# parrot_v2.net
KiCad netlist of a schematic drawn in EAGLE
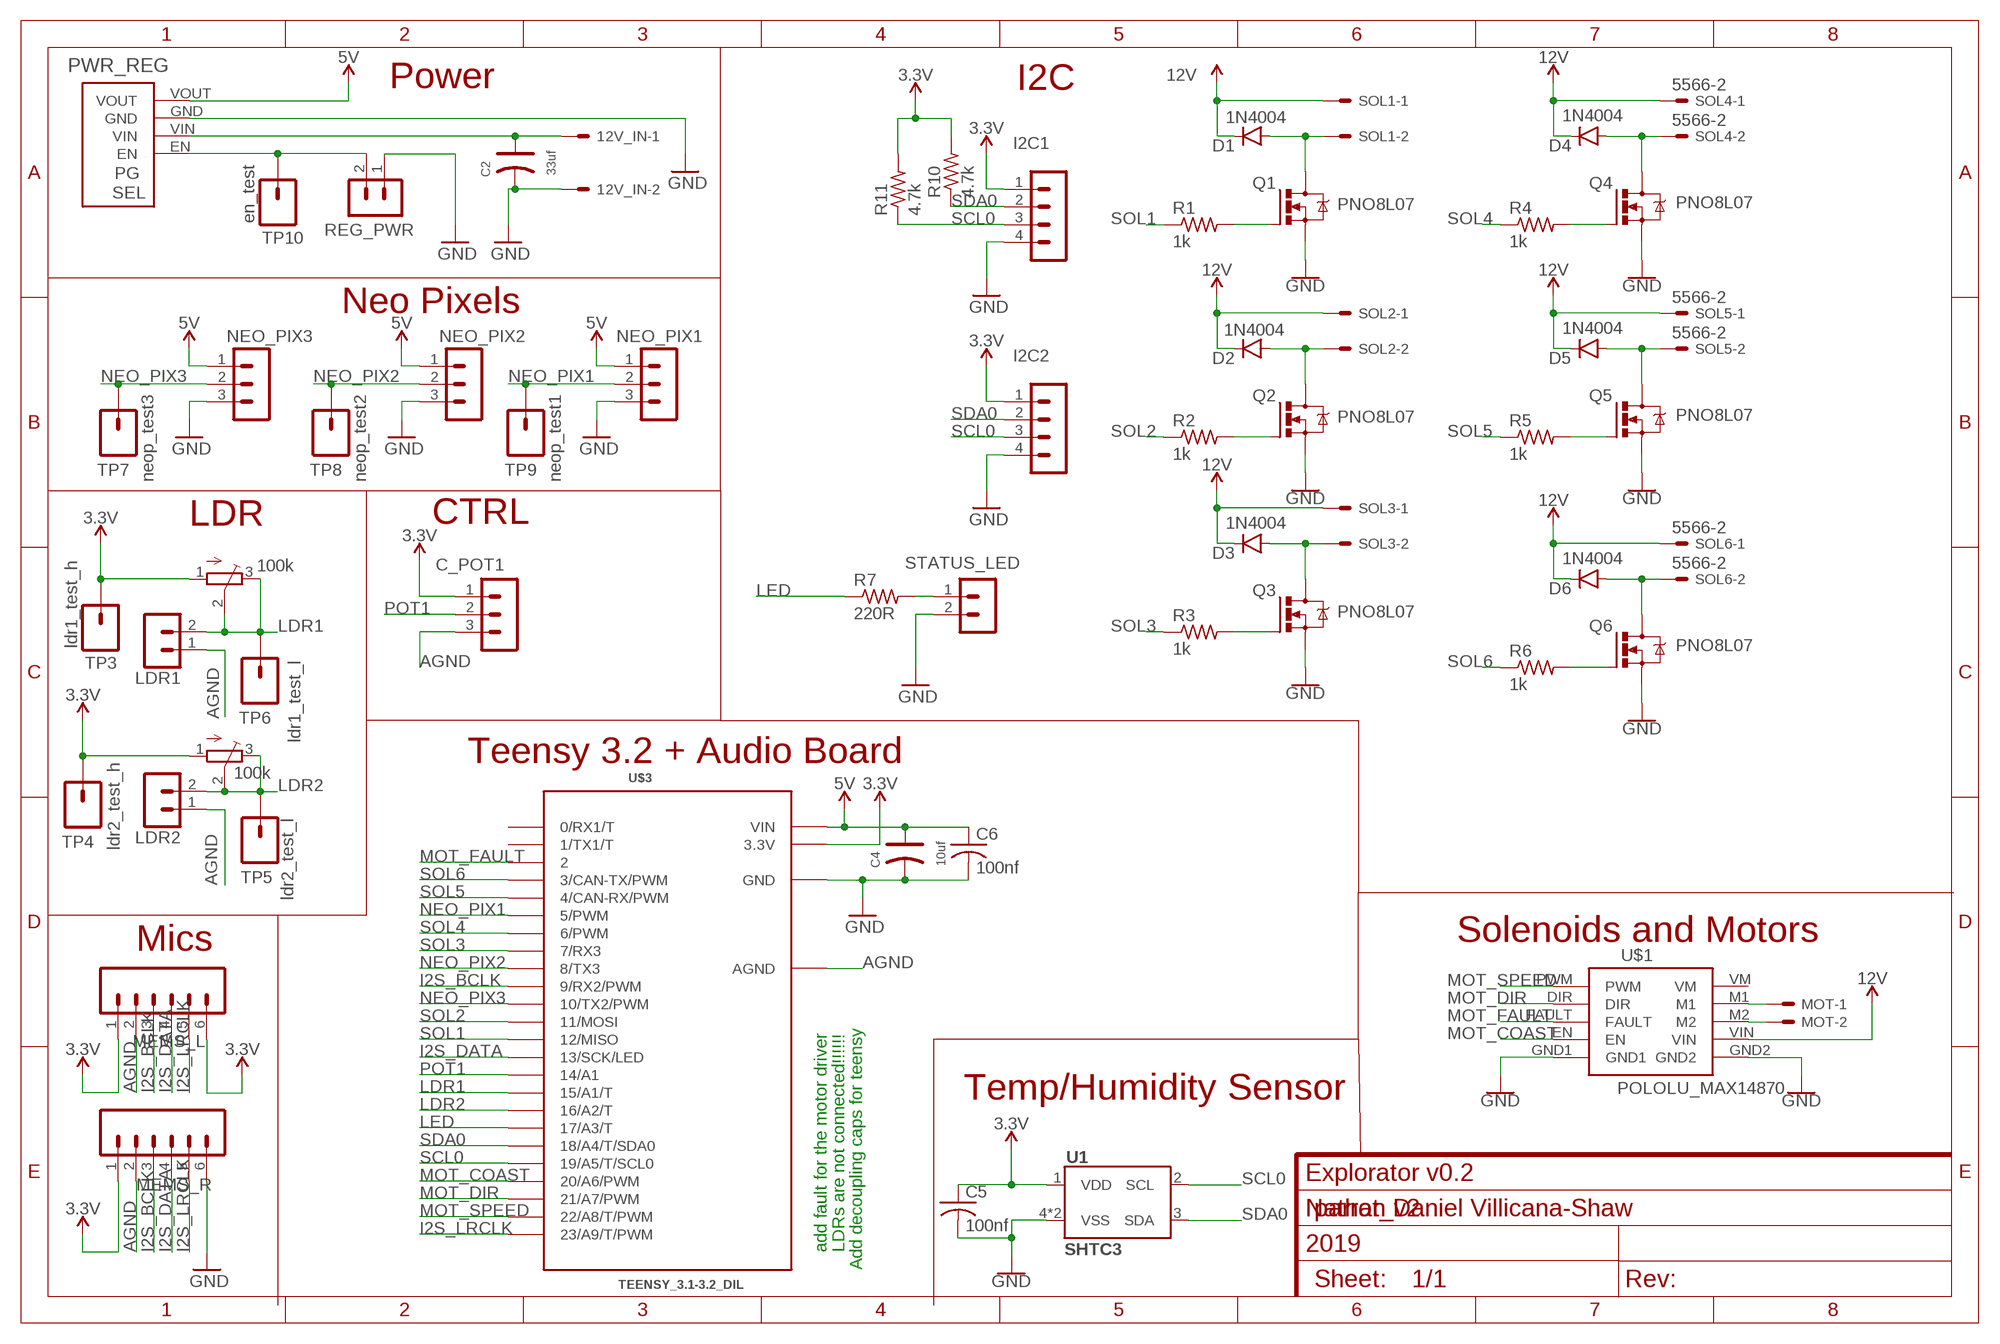
[diagram p0: schematic, sheet 1]

(export (version "E")
  (design (tool "Eeschema 10.0.6"))
  (components
    (comp (ref "12V_IN")
      (value "5566-2")
      (footprint "eagle-import:5566-2")
      (fields (field (name "MF") "MOLEX"))
      (libsource (lib "eagle-import") (part "5566-2"))
    )
    (comp (ref "C2")
      (value "33uf")
      (footprint "eagle-import:PC-D5.3MM")
      (fields (field (name "MPN") "KS 100uF/16V"))
      (libsource (lib "eagle-import") (part "DIP-ALUMINUM-47UF-16V(D5-H7MM)"))
    )
    (comp (ref "C4")
      (value "10uf")
      (footprint "eagle-import:PC-D5.3MM")
      (fields (field (name "MPN") "KS 100uF/16V"))
      (libsource (lib "eagle-import") (part "DIP-ALUMINUM-47UF-16V(D5-H7MM)"))
    )
    (comp (ref "C5")
      (value "100nf")
      (footprint "eagle-import:C2012")
      (libsource (lib "eagle-import") (part "C-USC2012"))
    )
    (comp (ref "C6")
      (value "100nf")
      (footprint "eagle-import:C2012")
      (libsource (lib "eagle-import") (part "C-USC2012"))
    )
    (comp (ref "C_POT1")
      (value "B3B-PH-K")
      (footprint "eagle-import:B3B-PH-K")
      (libsource (lib "eagle-import") (part "B3B-PH-K"))
    )
    (comp (ref "D1")
      (value "1N4004")
      (footprint "eagle-import:DIODE-1N4001")
      (libsource (lib "eagle-import") (part "DIODEPTH"))
    )
    (comp (ref "D2")
      (value "1N4004")
      (footprint "eagle-import:DIODE-1N4001")
      (libsource (lib "eagle-import") (part "DIODEPTH"))
    )
    (comp (ref "D3")
      (value "1N4004")
      (footprint "eagle-import:DIODE-1N4001")
      (libsource (lib "eagle-import") (part "DIODEPTH"))
    )
    (comp (ref "D4")
      (value "1N4004")
      (footprint "eagle-import:DIODE-1N4001")
      (libsource (lib "eagle-import") (part "DIODEPTH"))
    )
    (comp (ref "D5")
      (value "1N4004")
      (footprint "eagle-import:DIODE-1N4001")
      (libsource (lib "eagle-import") (part "DIODEPTH"))
    )
    (comp (ref "D6")
      (value "1N4004")
      (footprint "eagle-import:DIODE-1N4001")
      (libsource (lib "eagle-import") (part "DIODEPTH"))
    )
    (comp (ref "I2C1")
      (value "B4B-PH-K")
      (footprint "eagle-import:B4B-PH-K")
      (libsource (lib "eagle-import") (part "B4B-PH-K"))
    )
    (comp (ref "I2C2")
      (value "B4B-PH-K")
      (footprint "eagle-import:B4B-PH-K")
      (libsource (lib "eagle-import") (part "B4B-PH-K"))
    )
    (comp (ref "LDR1")
      (value "B2B-PH-K")
      (footprint "eagle-import:B2B-PH-K")
      (libsource (lib "eagle-import") (part "B2B-PH-K"))
    )
    (comp (ref "LDR2")
      (value "B2B-PH-K")
      (footprint "eagle-import:B2B-PH-K")
      (libsource (lib "eagle-import") (part "B2B-PH-K"))
    )
    (comp (ref "MEMS_L")
      (value "CONN_06POLAR")
      (footprint "eagle-import:MOLEX-1X6")
      (libsource (lib "eagle-import") (part "CONN_06POLAR"))
    )
    (comp (ref "MEMS_R")
      (value "CONN_06POLAR")
      (footprint "eagle-import:MOLEX-1X6")
      (libsource (lib "eagle-import") (part "CONN_06POLAR"))
    )
    (comp (ref "MOT")
      (value "5566-2")
      (footprint "eagle-import:5566-2")
      (fields (field (name "MF") "MOLEX"))
      (libsource (lib "eagle-import") (part "5566-2"))
    )
    (comp (ref "NEO_PIX1")
      (value "B3B-PH-K")
      (footprint "eagle-import:B3B-PH-K")
      (libsource (lib "eagle-import") (part "B3B-PH-K"))
    )
    (comp (ref "NEO_PIX2")
      (value "B3B-PH-K")
      (footprint "eagle-import:B3B-PH-K")
      (libsource (lib "eagle-import") (part "B3B-PH-K"))
    )
    (comp (ref "NEO_PIX3")
      (value "B3B-PH-K")
      (footprint "eagle-import:B3B-PH-K")
      (libsource (lib "eagle-import") (part "B3B-PH-K"))
    )
    (comp (ref "PWR_REG")
      (value "S9V11F5S6CMA_MISSINIG_PINS")
      (footprint "eagle-import:S9V11F3S5CMA_MISSING_PINS")
      (libsource (lib "eagle-import") (part "S9V11F5S6CMA_MISSINIG_PINS"))
    )
    (comp (ref "Q1")
      (value "PNO8L07")
      (footprint "eagle-import:TO220BV")
      (libsource (lib "eagle-import") (part "IRF540"))
    )
    (comp (ref "Q2")
      (value "PNO8L07")
      (footprint "eagle-import:TO220BV")
      (libsource (lib "eagle-import") (part "IRF540"))
    )
    (comp (ref "Q3")
      (value "PNO8L07")
      (footprint "eagle-import:TO220BV")
      (libsource (lib "eagle-import") (part "IRF540"))
    )
    (comp (ref "Q4")
      (value "PNO8L07")
      (footprint "eagle-import:TO220BV")
      (libsource (lib "eagle-import") (part "IRF540"))
    )
    (comp (ref "Q5")
      (value "PNO8L07")
      (footprint "eagle-import:TO220BV")
      (libsource (lib "eagle-import") (part "IRF540"))
    )
    (comp (ref "Q6")
      (value "PNO8L07")
      (footprint "eagle-import:TO220BV")
      (libsource (lib "eagle-import") (part "IRF540"))
    )
    (comp (ref "R1")
      (value "1k")
      (footprint "eagle-import:M1206")
      (libsource (lib "eagle-import") (part "R-US_M1206"))
    )
    (comp (ref "R2")
      (value "1k")
      (footprint "eagle-import:M1206")
      (libsource (lib "eagle-import") (part "R-US_M1206"))
    )
    (comp (ref "R3")
      (value "1k")
      (footprint "eagle-import:M1206")
      (libsource (lib "eagle-import") (part "R-US_M1206"))
    )
    (comp (ref "R4")
      (value "1k")
      (footprint "eagle-import:M1206")
      (libsource (lib "eagle-import") (part "R-US_M1206"))
    )
    (comp (ref "R5")
      (value "1k")
      (footprint "eagle-import:M1206")
      (libsource (lib "eagle-import") (part "R-US_M1206"))
    )
    (comp (ref "R6")
      (value "1k")
      (footprint "eagle-import:M1206")
      (libsource (lib "eagle-import") (part "R-US_M1206"))
    )
    (comp (ref "R7")
      (value "220R")
      (footprint "eagle-import:M1206")
      (libsource (lib "eagle-import") (part "R-US_M1206"))
    )
    (comp (ref "R10")
      (value "4.7k")
      (footprint "eagle-import:M1206")
      (libsource (lib "eagle-import") (part "R-US_M1206"))
    )
    (comp (ref "R11")
      (value "4.7k")
      (footprint "eagle-import:M1206")
      (libsource (lib "eagle-import") (part "R-US_M1206"))
    )
    (comp (ref "REG_PWR")
      (value "B2B-PH-K")
      (footprint "eagle-import:B2B-PH-K")
      (libsource (lib "eagle-import") (part "B2B-PH-K"))
    )
    (comp (ref "SOL1")
      (value "5566-2")
      (footprint "eagle-import:5566-2")
      (fields (field (name "MF") "MOLEX"))
      (libsource (lib "eagle-import") (part "5566-2"))
    )
    (comp (ref "SOL2")
      (value "5566-2")
      (footprint "eagle-import:5566-2")
      (fields (field (name "MF") "MOLEX"))
      (libsource (lib "eagle-import") (part "5566-2"))
    )
    (comp (ref "SOL3")
      (value "5566-2")
      (footprint "eagle-import:5566-2")
      (fields (field (name "MF") "MOLEX"))
      (libsource (lib "eagle-import") (part "5566-2"))
    )
    (comp (ref "SOL4")
      (value "5566-2")
      (footprint "eagle-import:5566-2")
      (fields (field (name "MF") "MOLEX"))
      (libsource (lib "eagle-import") (part "5566-2"))
    )
    (comp (ref "SOL5")
      (value "5566-2")
      (footprint "eagle-import:5566-2")
      (fields (field (name "MF") "MOLEX"))
      (libsource (lib "eagle-import") (part "5566-2"))
    )
    (comp (ref "SOL6")
      (value "5566-2")
      (footprint "eagle-import:5566-2")
      (fields (field (name "MF") "MOLEX"))
      (libsource (lib "eagle-import") (part "5566-2"))
    )
    (comp (ref "STATUS_LED")
      (value "B2B-PH-K")
      (footprint "eagle-import:B2B-PH-K")
      (libsource (lib "eagle-import") (part "B2B-PH-K"))
    )
    (comp (ref "TM1")
      (value "100k")
      (footprint "eagle-import:TC33X")
      (libsource (lib "eagle-import") (part "TRIMPOTTC33X"))
    )
    (comp (ref "TM2")
      (value "100k")
      (footprint "eagle-import:TC33X")
      (libsource (lib "eagle-import") (part "TRIMPOTTC33X"))
    )
    (comp (ref "TP3")
      (value "ldr1_test_h")
      (footprint "eagle-import:1X01")
      (libsource (lib "eagle-import") (part "CONN_01"))
    )
    (comp (ref "TP4")
      (value "ldr2_test_h")
      (footprint "eagle-import:1X01")
      (libsource (lib "eagle-import") (part "CONN_01"))
    )
    (comp (ref "TP5")
      (value "ldr2_test_l")
      (footprint "eagle-import:1X01")
      (libsource (lib "eagle-import") (part "CONN_01"))
    )
    (comp (ref "TP6")
      (value "ldr1_test_l")
      (footprint "eagle-import:1X01")
      (libsource (lib "eagle-import") (part "CONN_01"))
    )
    (comp (ref "TP7")
      (value "neop_test3")
      (footprint "eagle-import:1X01")
      (libsource (lib "eagle-import") (part "CONN_01"))
    )
    (comp (ref "TP8")
      (value "neop_test2")
      (footprint "eagle-import:1X01")
      (libsource (lib "eagle-import") (part "CONN_01"))
    )
    (comp (ref "TP9")
      (value "neop_test1")
      (footprint "eagle-import:1X01")
      (libsource (lib "eagle-import") (part "CONN_01"))
    )
    (comp (ref "TP10")
      (value "en_test")
      (footprint "eagle-import:1X01")
      (libsource (lib "eagle-import") (part "CONN_01"))
    )
    (comp (ref "U$1")
      (value "POLOLU_MAX14870")
      (footprint "eagle-import:POLOLU_MAX14870")
      (libsource (lib "eagle-import") (part "POLOLU_MAX14870"))
    )
    (comp (ref "U$3")
      (value "TEENSY_3.1-3.2_DIL")
      (footprint "eagle-import:TEENSY_3.0-3.2&LC_DIL")
      (libsource (lib "eagle-import") (part "TEENSY_3.1-3.2_DIL"))
    )
    (comp (ref "U1")
      (value "SHTC3")
      (footprint "eagle-import:SHTC3")
      (libsource (lib "eagle-import") (part "SHTC3"))
    )
  )
  (nets
    (net (code "1") (name "/AGND") (class "Default")
      (node (ref "C_POT1") (pin "3") (pinfunction "3_3") (pintype "passive"))
      (node (ref "LDR1") (pin "1") (pinfunction "1_1") (pintype "passive"))
      (node (ref "LDR2") (pin "1") (pinfunction "1_1") (pintype "passive"))
      (node (ref "MEMS_L") (pin "2") (pinfunction "2_2") (pintype "passive"))
      (node (ref "MEMS_R") (pin "2") (pinfunction "2_2") (pintype "passive"))
      (node (ref "U$3") (pin "AGND") (pinfunction "AGND_AGND") (pintype "power_in"))
    )
    (net (code "2") (name "/I2S_BCLK") (class "Default")
      (node (ref "MEMS_L") (pin "3") (pinfunction "3_3") (pintype "passive"))
      (node (ref "MEMS_R") (pin "3") (pinfunction "3_3") (pintype "passive"))
      (node (ref "U$3") (pin "9") (pinfunction "9/RX2/PWM_9") (pintype "bidirectional"))
    )
    (net (code "3") (name "/I2S_DATA") (class "Default")
      (node (ref "MEMS_L") (pin "4") (pinfunction "4_4") (pintype "passive"))
      (node (ref "MEMS_R") (pin "4") (pinfunction "4_4") (pintype "passive"))
      (node (ref "U$3") (pin "13") (pinfunction "13/SCK/LED_13") (pintype "bidirectional"))
    )
    (net (code "4") (name "/I2S_LRCLK") (class "Default")
      (node (ref "MEMS_L") (pin "5") (pinfunction "5_5") (pintype "passive"))
      (node (ref "MEMS_R") (pin "5") (pinfunction "5_5") (pintype "passive"))
      (node (ref "U$3") (pin "23/A9") (pinfunction "23/A9/T/PWM_23/A9") (pintype "bidirectional"))
    )
    (net (code "5") (name "/LDR1") (class "Default")
      (node (ref "LDR1") (pin "2") (pinfunction "2_2") (pintype "passive"))
      (node (ref "TM1") (pin "2") (pinfunction "S_2") (pintype "passive"))
      (node (ref "TM1") (pin "3") (pinfunction "E_3") (pintype "passive"))
      (node (ref "TP6") (pin "1") (pinfunction "1_1") (pintype "passive"))
      (node (ref "U$3") (pin "15/A1") (pinfunction "15/A1/T_15/A1") (pintype "bidirectional"))
    )
    (net (code "6") (name "/LDR2") (class "Default")
      (node (ref "LDR2") (pin "2") (pinfunction "2_2") (pintype "passive"))
      (node (ref "TM2") (pin "2") (pinfunction "S_2") (pintype "passive"))
      (node (ref "TM2") (pin "3") (pinfunction "E_3") (pintype "passive"))
      (node (ref "TP5") (pin "1") (pinfunction "1_1") (pintype "passive"))
      (node (ref "U$3") (pin "16/A2") (pinfunction "16/A2/T_16/A2") (pintype "bidirectional"))
    )
    (net (code "7") (name "/LED") (class "Default")
      (node (ref "R7") (pin "1") (pinfunction "1_1") (pintype "passive"))
      (node (ref "U$3") (pin "17/A3") (pinfunction "17/A3/T_17/A3") (pintype "bidirectional"))
    )
    (net (code "8") (name "/MOT_COAST") (class "Default")
      (node (ref "U$1") (pin "EN") (pinfunction "EN_EN") (pintype "bidirectional"))
      (node (ref "U$3") (pin "20/A6") (pinfunction "20/A6/PWM_20/A6") (pintype "bidirectional"))
    )
    (net (code "9") (name "/MOT_DIR") (class "Default")
      (node (ref "U$1") (pin "DIR") (pinfunction "DIR_DIR") (pintype "bidirectional"))
      (node (ref "U$3") (pin "21/A7") (pinfunction "21/A7/PWM_21/A7") (pintype "bidirectional"))
    )
    (net (code "10") (name "/MOT_FAULT") (class "Default")
      (node (ref "U$1") (pin "FAULT") (pinfunction "FAULT_FAULT") (pintype "bidirectional"))
      (node (ref "U$3") (pin "2") (pinfunction "2_2") (pintype "bidirectional"))
    )
    (net (code "11") (name "/MOT_SPEED") (class "Default")
      (node (ref "U$1") (pin "PWM") (pinfunction "PWM_PWM") (pintype "bidirectional"))
      (node (ref "U$3") (pin "22/A8") (pinfunction "22/A8/T/PWM_22/A8") (pintype "bidirectional"))
    )
    (net (code "12") (name "/NEO_PIX1") (class "Default")
      (node (ref "NEO_PIX1") (pin "2") (pinfunction "2_2") (pintype "passive"))
      (node (ref "TP9") (pin "1") (pinfunction "1_1") (pintype "passive"))
      (node (ref "U$3") (pin "5") (pinfunction "5/PWM_5") (pintype "bidirectional"))
    )
    (net (code "13") (name "/NEO_PIX2") (class "Default")
      (node (ref "NEO_PIX2") (pin "2") (pinfunction "2_2") (pintype "passive"))
      (node (ref "TP8") (pin "1") (pinfunction "1_1") (pintype "passive"))
      (node (ref "U$3") (pin "8") (pinfunction "8/TX3_8") (pintype "bidirectional"))
    )
    (net (code "14") (name "/NEO_PIX3") (class "Default")
      (node (ref "NEO_PIX3") (pin "2") (pinfunction "2_2") (pintype "passive"))
      (node (ref "TP7") (pin "1") (pinfunction "1_1") (pintype "passive"))
      (node (ref "U$3") (pin "10") (pinfunction "10/TX2/PWM_10") (pintype "bidirectional"))
    )
    (net (code "15") (name "/POT1") (class "Default")
      (node (ref "C_POT1") (pin "2") (pinfunction "2_2") (pintype "passive"))
      (node (ref "U$3") (pin "14/A0") (pinfunction "14/A1_14/A0") (pintype "bidirectional"))
    )
    (net (code "16") (name "/SCL0") (class "Default")
      (node (ref "I2C1") (pin "3") (pinfunction "3_3") (pintype "passive"))
      (node (ref "I2C2") (pin "3") (pinfunction "3_3") (pintype "passive"))
      (node (ref "R11") (pin "1") (pinfunction "1_1") (pintype "passive"))
      (node (ref "U$3") (pin "19/A5") (pinfunction "19/A5/T/SCL0_19/A5") (pintype "bidirectional"))
      (node (ref "U1") (pin "2") (pinfunction "SCL_2") (pintype "bidirectional"))
    )
    (net (code "17") (name "/SDA0") (class "Default")
      (node (ref "I2C1") (pin "2") (pinfunction "2_2") (pintype "passive"))
      (node (ref "I2C2") (pin "2") (pinfunction "2_2") (pintype "passive"))
      (node (ref "R10") (pin "1") (pinfunction "1_1") (pintype "passive"))
      (node (ref "U$3") (pin "18/A4") (pinfunction "18/A4/T/SDA0_18/A4") (pintype "bidirectional"))
      (node (ref "U1") (pin "3") (pinfunction "SDA_3") (pintype "bidirectional"))
    )
    (net (code "18") (name "/SOL1") (class "Default")
      (node (ref "R1") (pin "1") (pinfunction "1_1") (pintype "passive"))
      (node (ref "U$3") (pin "12") (pinfunction "12/MISO_12") (pintype "bidirectional"))
    )
    (net (code "19") (name "/SOL2") (class "Default")
      (node (ref "R2") (pin "1") (pinfunction "1_1") (pintype "passive"))
      (node (ref "U$3") (pin "11") (pinfunction "11/MOSI_11") (pintype "bidirectional"))
    )
    (net (code "20") (name "/SOL3") (class "Default")
      (node (ref "R3") (pin "1") (pinfunction "1_1") (pintype "passive"))
      (node (ref "U$3") (pin "7") (pinfunction "7/RX3_7") (pintype "bidirectional"))
    )
    (net (code "21") (name "/SOL4") (class "Default")
      (node (ref "R4") (pin "1") (pinfunction "1_1") (pintype "passive"))
      (node (ref "U$3") (pin "6") (pinfunction "6/PWM_6") (pintype "bidirectional"))
    )
    (net (code "22") (name "/SOL5") (class "Default")
      (node (ref "R5") (pin "1") (pinfunction "1_1") (pintype "passive"))
      (node (ref "U$3") (pin "4") (pinfunction "4/CAN-RX/PWM_4") (pintype "bidirectional"))
    )
    (net (code "23") (name "/SOL6") (class "Default")
      (node (ref "R6") (pin "1") (pinfunction "1_1") (pintype "passive"))
      (node (ref "U$3") (pin "3") (pinfunction "3/CAN-TX/PWM_3") (pintype "bidirectional"))
    )
    (net (code "24") (name "3.3V") (class "Default")
      (node (ref "C5") (pin "1") (pinfunction "1_1") (pintype "passive"))
      (node (ref "C_POT1") (pin "1") (pinfunction "1_1") (pintype "passive"))
      (node (ref "I2C1") (pin "1") (pinfunction "1_1") (pintype "passive"))
      (node (ref "I2C2") (pin "1") (pinfunction "1_1") (pintype "passive"))
      (node (ref "MEMS_L") (pin "1") (pinfunction "1_1") (pintype "passive"))
      (node (ref "MEMS_L") (pin "6") (pinfunction "6_6") (pintype "passive"))
      (node (ref "MEMS_R") (pin "1") (pinfunction "1_1") (pintype "passive"))
      (node (ref "R10") (pin "2") (pinfunction "2_2") (pintype "passive"))
      (node (ref "R11") (pin "2") (pinfunction "2_2") (pintype "passive"))
      (node (ref "TM1") (pin "1") (pinfunction "A_1") (pintype "passive"))
      (node (ref "TM2") (pin "1") (pinfunction "A_1") (pintype "passive"))
      (node (ref "TP3") (pin "1") (pinfunction "1_1") (pintype "passive"))
      (node (ref "TP4") (pin "1") (pinfunction "1_1") (pintype "passive"))
      (node (ref "U$3") (pin "3.3V") (pinfunction "3.3V_3.3V") (pintype "power_in"))
      (node (ref "U1") (pin "1") (pinfunction "VDD_1") (pintype "bidirectional"))
    )
    (net (code "25") (name "5V") (class "Default")
      (node (ref "C4") (pin "+") (pinfunction "+_+") (pintype "passive"))
      (node (ref "C6") (pin "1") (pinfunction "1_1") (pintype "passive"))
      (node (ref "NEO_PIX1") (pin "1") (pinfunction "1_1") (pintype "passive"))
      (node (ref "NEO_PIX2") (pin "1") (pinfunction "1_1") (pintype "passive"))
      (node (ref "NEO_PIX3") (pin "1") (pinfunction "1_1") (pintype "passive"))
      (node (ref "PWR_REG") (pin "VOUT") (pinfunction "VOUT_VOUT") (pintype "bidirectional"))
      (node (ref "U$3") (pin "VIN") (pinfunction "VIN_VIN") (pintype "power_in"))
    )
    (net (code "26") (name "12V") (class "Default")
      (node (ref "12V_IN") (pin "1") (pinfunction "S_1") (pintype "passive"))
      (node (ref "C2") (pin "+") (pinfunction "+_+") (pintype "passive"))
      (node (ref "D1") (pin "C") (pinfunction "C_C") (pintype "passive"))
      (node (ref "D2") (pin "C") (pinfunction "C_C") (pintype "passive"))
      (node (ref "D3") (pin "C") (pinfunction "C_C") (pintype "passive"))
      (node (ref "D4") (pin "C") (pinfunction "C_C") (pintype "passive"))
      (node (ref "D5") (pin "C") (pinfunction "C_C") (pintype "passive"))
      (node (ref "D6") (pin "C") (pinfunction "C_C") (pintype "passive"))
      (node (ref "PWR_REG") (pin "VIN") (pinfunction "VIN_VIN") (pintype "bidirectional"))
      (node (ref "SOL1") (pin "1") (pinfunction "S_1") (pintype "passive"))
      (node (ref "SOL2") (pin "1") (pinfunction "S_1") (pintype "passive"))
      (node (ref "SOL3") (pin "1") (pinfunction "S_1") (pintype "passive"))
      (node (ref "SOL4") (pin "1") (pinfunction "S_1") (pintype "passive"))
      (node (ref "SOL5") (pin "1") (pinfunction "S_1") (pintype "passive"))
      (node (ref "SOL6") (pin "1") (pinfunction "S_1") (pintype "passive"))
      (node (ref "U$1") (pin "VIN") (pinfunction "VIN_VIN") (pintype "bidirectional"))
    )
    (net (code "27") (name "GND") (class "Default")
      (node (ref "12V_IN") (pin "2") (pinfunction "S_2") (pintype "passive"))
      (node (ref "C2") (pin "-") (pinfunction "-_-") (pintype "passive"))
      (node (ref "C4") (pin "-") (pinfunction "-_-") (pintype "passive"))
      (node (ref "C5") (pin "2") (pinfunction "2_2") (pintype "passive"))
      (node (ref "C6") (pin "2") (pinfunction "2_2") (pintype "passive"))
      (node (ref "I2C1") (pin "4") (pinfunction "4_4") (pintype "passive"))
      (node (ref "I2C2") (pin "4") (pinfunction "4_4") (pintype "passive"))
      (node (ref "MEMS_R") (pin "6") (pinfunction "6_6") (pintype "passive"))
      (node (ref "NEO_PIX1") (pin "3") (pinfunction "3_3") (pintype "passive"))
      (node (ref "NEO_PIX2") (pin "3") (pinfunction "3_3") (pintype "passive"))
      (node (ref "NEO_PIX3") (pin "3") (pinfunction "3_3") (pintype "passive"))
      (node (ref "PWR_REG") (pin "GND") (pinfunction "GND_GND") (pintype "bidirectional"))
      (node (ref "Q1") (pin "S") (pinfunction "S_S") (pintype "passive"))
      (node (ref "Q2") (pin "S") (pinfunction "S_S") (pintype "passive"))
      (node (ref "Q3") (pin "S") (pinfunction "S_S") (pintype "passive"))
      (node (ref "Q4") (pin "S") (pinfunction "S_S") (pintype "passive"))
      (node (ref "Q5") (pin "S") (pinfunction "S_S") (pintype "passive"))
      (node (ref "Q6") (pin "S") (pinfunction "S_S") (pintype "passive"))
      (node (ref "REG_PWR") (pin "1") (pinfunction "1_1") (pintype "passive"))
      (node (ref "STATUS_LED") (pin "2") (pinfunction "2_2") (pintype "passive"))
      (node (ref "U$1") (pin "GND1") (pinfunction "GND1_GND1") (pintype "bidirectional"))
      (node (ref "U$1") (pin "GND2") (pinfunction "GND2_GND2") (pintype "bidirectional"))
      (node (ref "U$3") (pin "GND") (pinfunction "GND_GND") (pintype "power_in"))
      (node (ref "U1") (pin "4") (pinfunction "VSS_4") (pintype "bidirectional"))
      (node (ref "U1") (pin "5") (pinfunction "VSS_5") (pintype "bidirectional"))
    )
    (net (code "28") (name "Net-(MOTA-S)") (class "Default")
      (node (ref "MOT") (pin "1") (pinfunction "S_1") (pintype "passive"))
      (node (ref "U$1") (pin "M1") (pinfunction "M1_M1") (pintype "bidirectional"))
    )
    (net (code "29") (name "Net-(MOTB-S)") (class "Default")
      (node (ref "MOT") (pin "2") (pinfunction "S_2") (pintype "passive"))
      (node (ref "U$1") (pin "M2") (pinfunction "M2_M2") (pintype "bidirectional"))
    )
    (net (code "30") (name "Net-(PWR_REG-PadEN)") (class "Default")
      (node (ref "PWR_REG") (pin "EN") (pinfunction "EN_EN") (pintype "bidirectional"))
      (node (ref "REG_PWR") (pin "2") (pinfunction "2_2") (pintype "passive"))
      (node (ref "TP10") (pin "1") (pinfunction "1_1") (pintype "passive"))
    )
    (net (code "31") (name "Net-(Q1-PadG)") (class "Default")
      (node (ref "Q1") (pin "G") (pinfunction "G_G") (pintype "passive"))
      (node (ref "R1") (pin "2") (pinfunction "2_2") (pintype "passive"))
    )
    (net (code "32") (name "Net-(Q2-PadG)") (class "Default")
      (node (ref "Q2") (pin "G") (pinfunction "G_G") (pintype "passive"))
      (node (ref "R2") (pin "2") (pinfunction "2_2") (pintype "passive"))
    )
    (net (code "33") (name "Net-(Q3-PadG)") (class "Default")
      (node (ref "Q3") (pin "G") (pinfunction "G_G") (pintype "passive"))
      (node (ref "R3") (pin "2") (pinfunction "2_2") (pintype "passive"))
    )
    (net (code "34") (name "Net-(Q4-PadG)") (class "Default")
      (node (ref "Q4") (pin "G") (pinfunction "G_G") (pintype "passive"))
      (node (ref "R4") (pin "2") (pinfunction "2_2") (pintype "passive"))
    )
    (net (code "35") (name "Net-(Q5-PadG)") (class "Default")
      (node (ref "Q5") (pin "G") (pinfunction "G_G") (pintype "passive"))
      (node (ref "R5") (pin "2") (pinfunction "2_2") (pintype "passive"))
    )
    (net (code "36") (name "Net-(Q6-PadG)") (class "Default")
      (node (ref "Q6") (pin "G") (pinfunction "G_G") (pintype "passive"))
      (node (ref "R6") (pin "2") (pinfunction "2_2") (pintype "passive"))
    )
    (net (code "37") (name "Net-(R7-Pad2)") (class "Default")
      (node (ref "R7") (pin "2") (pinfunction "2_2") (pintype "passive"))
      (node (ref "STATUS_LED") (pin "1") (pinfunction "1_1") (pintype "passive"))
    )
    (net (code "38") (name "Net-(SOL1B-S)") (class "Default")
      (node (ref "D1") (pin "A") (pinfunction "A_A") (pintype "passive"))
      (node (ref "Q1") (pin "D") (pinfunction "D_D") (pintype "passive"))
      (node (ref "SOL1") (pin "2") (pinfunction "S_2") (pintype "passive"))
    )
    (net (code "39") (name "Net-(SOL2B-S)") (class "Default")
      (node (ref "D2") (pin "A") (pinfunction "A_A") (pintype "passive"))
      (node (ref "Q2") (pin "D") (pinfunction "D_D") (pintype "passive"))
      (node (ref "SOL2") (pin "2") (pinfunction "S_2") (pintype "passive"))
    )
    (net (code "40") (name "Net-(SOL3B-S)") (class "Default")
      (node (ref "D3") (pin "A") (pinfunction "A_A") (pintype "passive"))
      (node (ref "Q3") (pin "D") (pinfunction "D_D") (pintype "passive"))
      (node (ref "SOL3") (pin "2") (pinfunction "S_2") (pintype "passive"))
    )
    (net (code "41") (name "Net-(SOL4B-S)") (class "Default")
      (node (ref "D4") (pin "A") (pinfunction "A_A") (pintype "passive"))
      (node (ref "Q4") (pin "D") (pinfunction "D_D") (pintype "passive"))
      (node (ref "SOL4") (pin "2") (pinfunction "S_2") (pintype "passive"))
    )
    (net (code "42") (name "Net-(SOL5B-S)") (class "Default")
      (node (ref "D5") (pin "A") (pinfunction "A_A") (pintype "passive"))
      (node (ref "Q5") (pin "D") (pinfunction "D_D") (pintype "passive"))
      (node (ref "SOL5") (pin "2") (pinfunction "S_2") (pintype "passive"))
    )
    (net (code "43") (name "Net-(SOL6B-S)") (class "Default")
      (node (ref "D6") (pin "A") (pinfunction "A_A") (pintype "passive"))
      (node (ref "Q6") (pin "D") (pinfunction "D_D") (pintype "passive"))
      (node (ref "SOL6") (pin "2") (pinfunction "S_2") (pintype "passive"))
    )
    (net (code "44") (name "unconnected-(U$1-PadVM)") (class "Default")
      (node (ref "U$1") (pin "VM") (pinfunction "VM_VM") (pintype "bidirectional"))
    )
    (net (code "45") (name "unconnected-(U$3-0{slash}RX1{slash}T-Pad0)") (class "Default")
      (node (ref "U$3") (pin "0") (pinfunction "0/RX1/T_0") (pintype "bidirectional"))
    )
    (net (code "46") (name "unconnected-(U$3-1{slash}TX1{slash}T-Pad1)") (class "Default")
      (node (ref "U$3") (pin "1") (pinfunction "1/TX1/T_1") (pintype "bidirectional"))
    )
  )
)
